# heater.net
KiCad netlist of a schematic drawn in Altium Designer
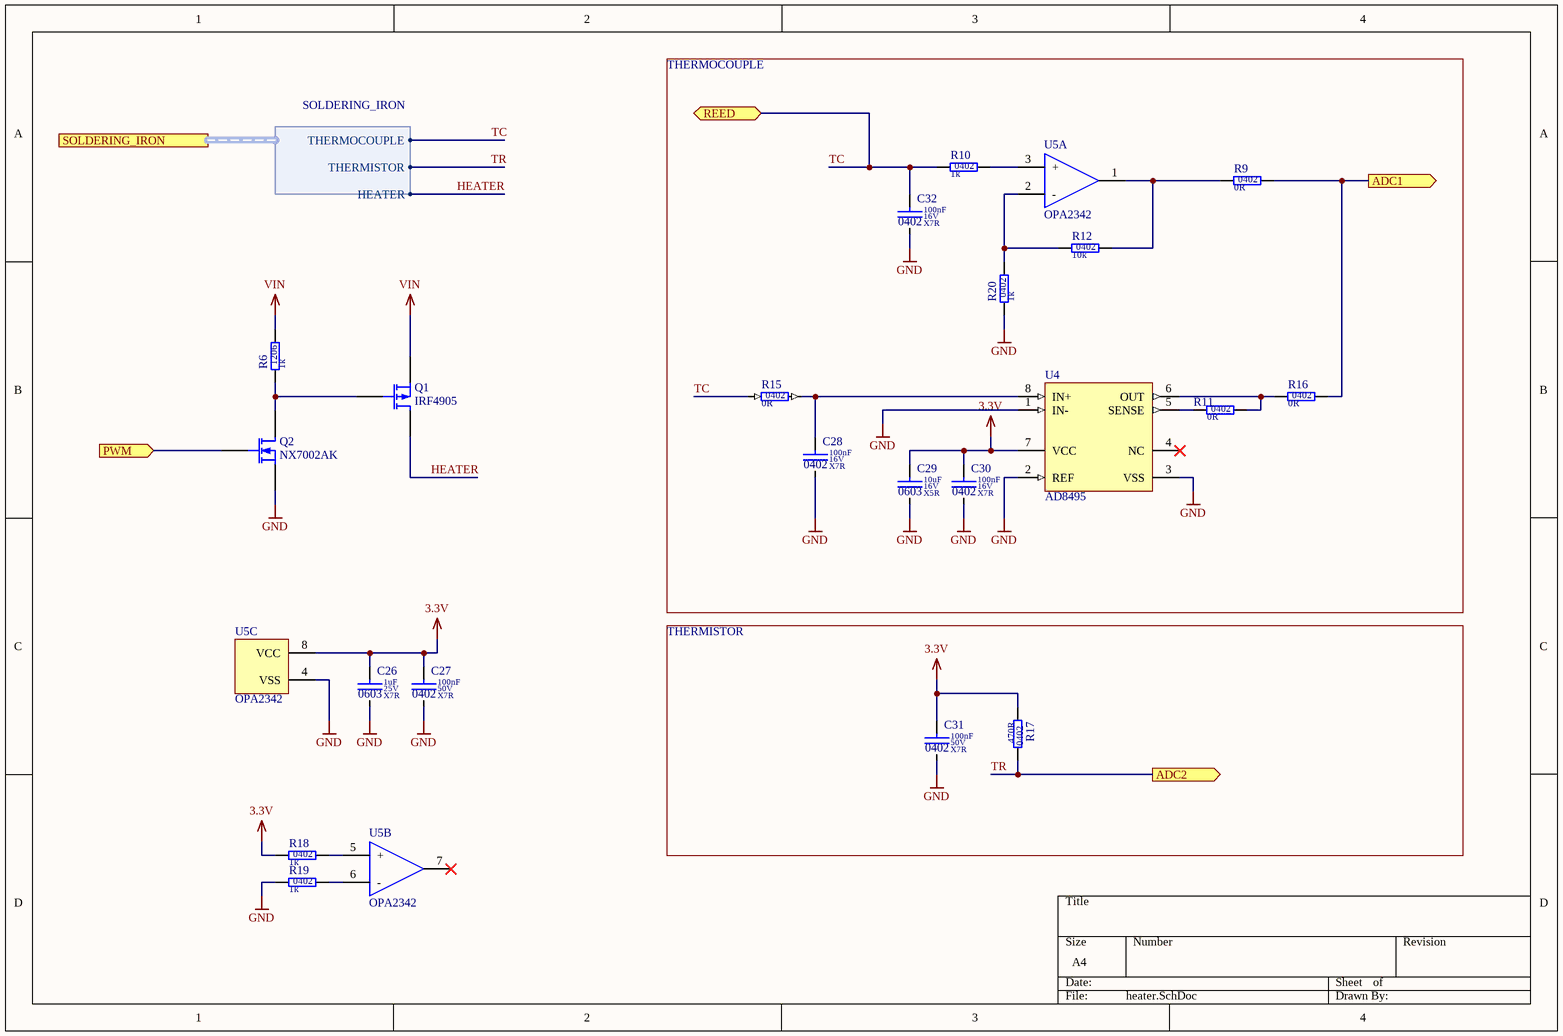
[diagram p0: heater.SchDoc]

(export (version "E")
  (design (tool "Eeschema 10.0.6"))
  (components
    (comp (ref "C26")
      (value "1uF")
      (footprint "C_0603_1608")
      (description "Capacitor")
      (fields
        (field (name "DIELECTRIC") "X7R")
        (field (name "VOLTAGE") "25V")
        (field (name "SCH_FOOTPRINT") "0603")
        (field (name "PART NUMBER") "C_1uF_25V_X7R_0603_10")
        (field (name "MANUFACTURER") "Samsung")
      )
      (libsource (lib "Library") (part "C"))
    )
    (comp (ref "C27")
      (value "100nF")
      (footprint "C_0402_1005")
      (description "Capacitor")
      (fields
        (field (name "DIELECTRIC") "X7R")
        (field (name "VOLTAGE") "50V")
        (field (name "SCH_FOOTPRINT") "0402")
        (field (name "PART NUMBER") "C_100nF_50V_X7R_0402_10")
        (field (name "MANUFACTURER") "Murata")
      )
      (libsource (lib "Library") (part "C"))
    )
    (comp (ref "C28")
      (value "100nF")
      (footprint "C_0402_1005")
      (description "Capacitor")
      (fields
        (field (name "DIELECTRIC") "X7R")
        (field (name "VOLTAGE") "16V")
        (field (name "SCH_FOOTPRINT") "0402")
        (field (name "PART NUMBER") "C_100nF_16V_X7R_0402_10")
        (field (name "MANUFACTURER") "Murata")
      )
      (libsource (lib "Library") (part "C"))
    )
    (comp (ref "C29")
      (value "10uF")
      (footprint "C_0603_1608")
      (description "Capacitor")
      (fields
        (field (name "DIELECTRIC") "X5R")
        (field (name "VOLTAGE") "16V")
        (field (name "SCH_FOOTPRINT") "0603")
        (field (name "PART NUMBER") "C_10uF_16V_X5R_0603_20")
        (field (name "MANUFACTURER") "Samsung Electro-Mechanics")
      )
      (libsource (lib "Library") (part "C"))
    )
    (comp (ref "C30")
      (value "100nF")
      (footprint "C_0402_1005")
      (description "Capacitor")
      (fields
        (field (name "DIELECTRIC") "X7R")
        (field (name "VOLTAGE") "16V")
        (field (name "SCH_FOOTPRINT") "0402")
        (field (name "PART NUMBER") "C_100nF_16V_X7R_0402_10")
        (field (name "MANUFACTURER") "Murata")
      )
      (libsource (lib "Library") (part "C"))
    )
    (comp (ref "C31")
      (value "100nF")
      (footprint "C_0402_1005")
      (description "Capacitor")
      (fields
        (field (name "DIELECTRIC") "X7R")
        (field (name "VOLTAGE") "50V")
        (field (name "SCH_FOOTPRINT") "0402")
        (field (name "PART NUMBER") "C_100nF_50V_X7R_0402_10")
        (field (name "MANUFACTURER") "Murata")
      )
      (libsource (lib "Library") (part "C"))
    )
    (comp (ref "C32")
      (value "100nF")
      (footprint "C_0402_1005")
      (description "Capacitor")
      (fields
        (field (name "DIELECTRIC") "X7R")
        (field (name "VOLTAGE") "16V")
        (field (name "SCH_FOOTPRINT") "0402")
        (field (name "PART NUMBER") "C_100nF_16V_X7R_0402_10")
        (field (name "MANUFACTURER") "Murata")
      )
      (libsource (lib "Library") (part "C"))
    )
    (comp (ref "Q1")
      (value "IRF4905")
      (footprint "IRF4905")
      (description "PMOS TO-220")
      (libsource (lib "soldering_station") (part "IRF4905"))
    )
    (comp (ref "Q2")
      (value "NX7002AK")
      (footprint "NX7002AK.215")
      (description "Tranzystor: N-MOSFET; unipolarny; 60V; 0,12A; 325mW; SOT23")
      (libsource (lib "soldering_station") (part "NX7002AK.215"))
    )
    (comp (ref "R6")
      (value "1k")
      (footprint "R_1206_3216")
      (fields
        (field (name "SCH_FOOTPRINT") "1206")
        (field (name "PART NUMBER") "R_47k_1206_1")
        (field (name "VOLTAGE") "200V")
        (field (name "POWER") "500mW")
      )
      (libsource (lib "Library") (part "R"))
    )
    (comp (ref "R9")
      (value "0R")
      (footprint "R_0402_1005")
      (fields
        (field (name "SCH_FOOTPRINT") "0402")
        (field (name "PART NUMBER") "R_0R_0402_5")
        (field (name "VOLTAGE") "50V")
        (field (name "POWER") "100mW")
      )
      (libsource (lib "Library") (part "R"))
    )
    (comp (ref "R10")
      (value "1k")
      (footprint "R_0402_1005")
      (fields
        (field (name "SCH_FOOTPRINT") "0402")
        (field (name "PART NUMBER") "R_1k_0402_1")
        (field (name "VOLTAGE") "50V")
        (field (name "POWER") "63mW")
      )
      (libsource (lib "Library") (part "R"))
    )
    (comp (ref "R11")
      (value "0R")
      (footprint "R_0402_1005")
      (fields
        (field (name "SCH_FOOTPRINT") "0402")
        (field (name "PART NUMBER") "R_0R_0402_5")
        (field (name "VOLTAGE") "50V")
        (field (name "POWER") "100mW")
      )
      (libsource (lib "Library") (part "R"))
    )
    (comp (ref "R12")
      (value "10k")
      (footprint "R_0402_1005")
      (fields
        (field (name "SCH_FOOTPRINT") "0402")
        (field (name "PART NUMBER") "R_10k_0402_1")
        (field (name "VOLTAGE") "50V")
        (field (name "POWER") "63mW")
      )
      (libsource (lib "Library") (part "R"))
    )
    (comp (ref "R15")
      (value "0R")
      (footprint "R_0402_1005")
      (fields
        (field (name "SCH_FOOTPRINT") "0402")
        (field (name "PART NUMBER") "R_0R_0402_5")
        (field (name "VOLTAGE") "50V")
        (field (name "POWER") "100mW")
      )
      (libsource (lib "") (part "R_1"))
    )
    (comp (ref "R16")
      (value "0R")
      (footprint "R_0402_1005")
      (fields
        (field (name "SCH_FOOTPRINT") "0402")
        (field (name "PART NUMBER") "R_0R_0402_5")
        (field (name "VOLTAGE") "50V")
        (field (name "POWER") "100mW")
      )
      (libsource (lib "Library") (part "R"))
    )
    (comp (ref "R17")
      (value "470R")
      (footprint "R_0402_1005")
      (fields
        (field (name "SCH_FOOTPRINT") "0402")
        (field (name "PART NUMBER") "R_470R_0402_1")
        (field (name "VOLTAGE") "50V")
        (field (name "POWER") "63mW")
      )
      (libsource (lib "Library") (part "R"))
    )
    (comp (ref "R18")
      (value "1k")
      (footprint "R_0402_1005")
      (fields
        (field (name "SCH_FOOTPRINT") "0402")
        (field (name "PART NUMBER") "R_1k_0402_1")
        (field (name "VOLTAGE") "50V")
        (field (name "POWER") "63mW")
      )
      (libsource (lib "Library") (part "R"))
    )
    (comp (ref "R19")
      (value "1k")
      (footprint "R_0402_1005")
      (fields
        (field (name "SCH_FOOTPRINT") "0402")
        (field (name "PART NUMBER") "R_1k_0402_1")
        (field (name "VOLTAGE") "50V")
        (field (name "POWER") "63mW")
      )
      (libsource (lib "Library") (part "R"))
    )
    (comp (ref "R20")
      (value "1k")
      (footprint "R_0402_1005")
      (fields
        (field (name "SCH_FOOTPRINT") "0402")
        (field (name "PART NUMBER") "R_1k_0402_1")
        (field (name "VOLTAGE") "50V")
        (field (name "POWER") "63mW")
      )
      (libsource (lib "Library") (part "R"))
    )
    (comp (ref "U4")
      (value "AD8495")
      (footprint "AD8494")
      (description "Precision Thermocouple Amplifiers\r\nwith Cold Junction Compensation")
      (libsource (lib "soldering_station") (part "AD8495"))
    )
    (comp (ref "U5")
      (value "OPA2342")
      (footprint "OPA2342")
      (description "Wzmacniacz operacyjny; 1MHz; 2,7÷5,5V; Kanały: 2; SO8")
      (libsource (lib "soldering_station") (part "OPA2342"))
    )
  )
  (nets
    (net (code "2") (name "/ADC1") (class "Default")
      (node (ref "R16") (pin "2") (pinfunction "2_2") (pintype "passive"))
      (node (ref "R9") (pin "2") (pinfunction "2_2") (pintype "passive"))
    )
    (net (code "3") (name "/HEATER") (class "Default")
      (node (ref "Q1") (pin "2") (pinfunction "D_2") (pintype "passive"))
    )
    (net (code "4") (name "/PWM") (class "Default")
      (node (ref "Q2") (pin "1") (pinfunction "G_1") (pintype "passive"))
    )
    (net (code "5") (name "/TC") (class "Default")
      (node (ref "C32") (pin "1") (pinfunction "1_1") (pintype "passive"))
      (node (ref "R10") (pin "1") (pinfunction "1_1") (pintype "passive"))
      (node (ref "R15") (pin "1") (pinfunction "1_1") (pintype "input"))
    )
    (net (code "6") (name "/TR") (class "Default")
      (node (ref "R17") (pin "2") (pinfunction "2_2") (pintype "passive"))
    )
    (net (code "8") (name "3.3V") (class "Default")
      (node (ref "C26") (pin "1") (pinfunction "1_1") (pintype "passive"))
      (node (ref "C27") (pin "1") (pinfunction "1_1") (pintype "passive"))
      (node (ref "C29") (pin "1") (pinfunction "1_1") (pintype "passive"))
      (node (ref "C30") (pin "1") (pinfunction "1_1") (pintype "passive"))
      (node (ref "C31") (pin "1") (pinfunction "1_1") (pintype "passive"))
      (node (ref "R17") (pin "1") (pinfunction "1_1") (pintype "passive"))
      (node (ref "R18") (pin "1") (pinfunction "1_1") (pintype "passive"))
      (node (ref "U4") (pin "7") (pinfunction "VCC_7") (pintype "power_in"))
      (node (ref "U5") (pin "8") (pinfunction "VCC_8") (pintype "power_in"))
    )
    (net (code "9") (name "GND") (class "Default")
      (node (ref "C26") (pin "2") (pinfunction "2_2") (pintype "passive"))
      (node (ref "C27") (pin "2") (pinfunction "2_2") (pintype "passive"))
      (node (ref "C28") (pin "2") (pinfunction "2_2") (pintype "passive"))
      (node (ref "C29") (pin "2") (pinfunction "2_2") (pintype "passive"))
      (node (ref "C30") (pin "2") (pinfunction "2_2") (pintype "passive"))
      (node (ref "C31") (pin "2") (pinfunction "2_2") (pintype "passive"))
      (node (ref "C32") (pin "2") (pinfunction "2_2") (pintype "passive"))
      (node (ref "Q2") (pin "2") (pinfunction "S_2") (pintype "passive"))
      (node (ref "R19") (pin "1") (pinfunction "1_1") (pintype "passive"))
      (node (ref "R20") (pin "1") (pinfunction "1_1") (pintype "passive"))
      (node (ref "U4") (pin "1") (pinfunction "IN-_1") (pintype "input"))
      (node (ref "U4") (pin "2") (pinfunction "REF_2") (pintype "input"))
      (node (ref "U4") (pin "3") (pinfunction "VSS_3") (pintype "power_in"))
      (node (ref "U5") (pin "4") (pinfunction "VSS_4") (pintype "power_in"))
    )
    (net (code "10") (name "Net-(Q1-G)") (class "Default")
      (node (ref "Q1") (pin "1") (pinfunction "G_1") (pintype "passive"))
      (node (ref "Q2") (pin "3") (pinfunction "D_3") (pintype "passive"))
      (node (ref "R6") (pin "1") (pinfunction "1_1") (pintype "passive"))
    )
    (net (code "11") (name "Net-(U4-IN+)") (class "Default")
      (node (ref "C28") (pin "1") (pinfunction "1_1") (pintype "passive"))
      (node (ref "R15") (pin "2") (pinfunction "2_2") (pintype "output"))
      (node (ref "U4") (pin "8") (pinfunction "IN+_8") (pintype "input"))
    )
    (net (code "12") (name "Net-(U4-OUT)") (class "Default")
      (node (ref "R11") (pin "2") (pinfunction "2_2") (pintype "passive"))
      (node (ref "R16") (pin "1") (pinfunction "1_1") (pintype "passive"))
      (node (ref "U4") (pin "6") (pinfunction "OUT_6") (pintype "output"))
    )
    (net (code "13") (name "Net-(U4-SENSE)") (class "Default")
      (node (ref "R11") (pin "1") (pinfunction "1_1") (pintype "passive"))
      (node (ref "U4") (pin "5") (pinfunction "SENSE_5") (pintype "output"))
    )
    (net (code "14") (name "Net-(U5A-+)") (class "Default")
      (node (ref "R10") (pin "2") (pinfunction "2_2") (pintype "passive"))
      (node (ref "U5") (pin "3") (pinfunction "+_3") (pintype "passive"))
    )
    (net (code "15") (name "Net-(U5A--)") (class "Default")
      (node (ref "R12") (pin "1") (pinfunction "1_1") (pintype "passive"))
      (node (ref "R20") (pin "2") (pinfunction "2_2") (pintype "passive"))
      (node (ref "U5") (pin "2") (pinfunction "-_2") (pintype "passive"))
    )
    (net (code "16") (name "Net-(U5A-OUT)") (class "Default")
      (node (ref "R12") (pin "2") (pinfunction "2_2") (pintype "passive"))
      (node (ref "R9") (pin "1") (pinfunction "1_1") (pintype "passive"))
      (node (ref "U5") (pin "1") (pinfunction "OUT_1") (pintype "passive"))
    )
    (net (code "17") (name "Net-(U5B-+)") (class "Default")
      (node (ref "R18") (pin "2") (pinfunction "2_2") (pintype "passive"))
      (node (ref "U5") (pin "5") (pinfunction "+_5") (pintype "passive"))
    )
    (net (code "18") (name "Net-(U5B--)") (class "Default")
      (node (ref "R19") (pin "2") (pinfunction "2_2") (pintype "passive"))
      (node (ref "U5") (pin "6") (pinfunction "-_6") (pintype "passive"))
    )
    (net (code "19") (name "VIN") (class "Default")
      (node (ref "Q1") (pin "3") (pinfunction "S_3") (pintype "passive"))
      (node (ref "R6") (pin "2") (pinfunction "2_2") (pintype "passive"))
    )
    (net (code "20") (name "unconnected-(U4-NC-Pad4)") (class "Default")
      (node (ref "U4") (pin "4") (pinfunction "NC_4") (pintype "passive+no_connect"))
    )
    (net (code "21") (name "unconnected-(U5B-OUT-Pad7)") (class "Default")
      (node (ref "U5") (pin "7") (pinfunction "OUT_7") (pintype "passive+no_connect"))
    )
  )
)
